# connectors-hw.net
KiCad netlist of a schematic drawn in Altium Designer
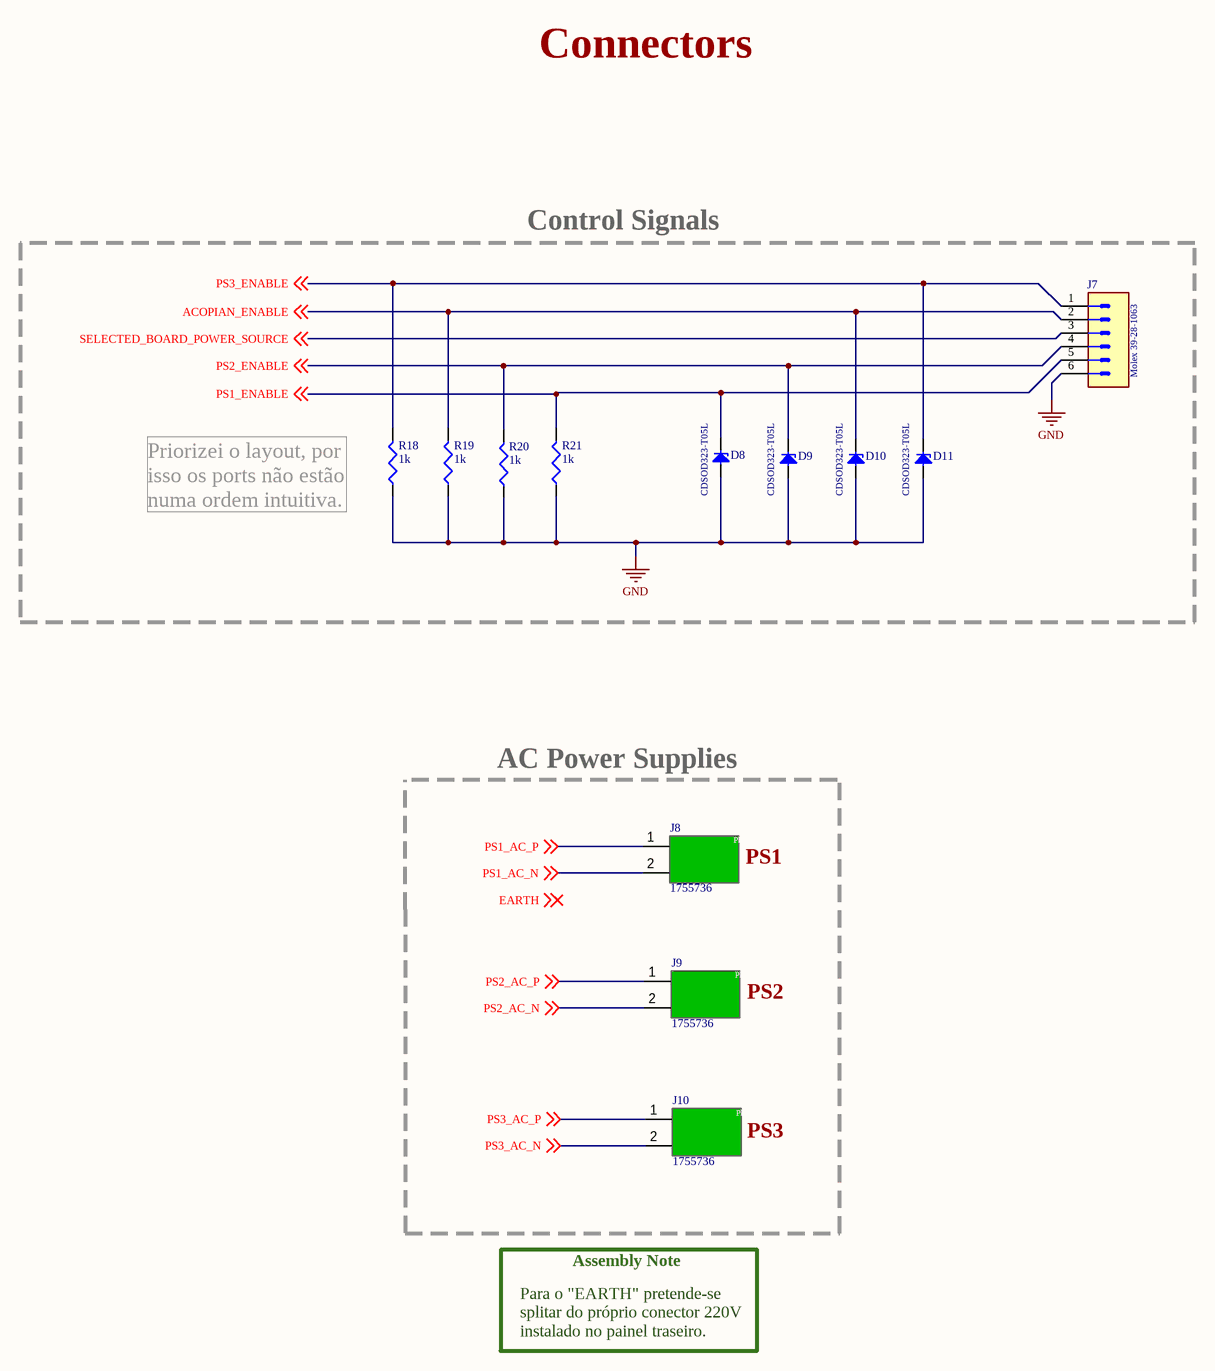
[diagram p0: connectors-hw.SchDoc]

(export (version "E")
  (design (tool "Eeschema 10.0.6"))
  (components
    (comp (ref "D8")
      (value "CDSOD323-T05L")
      (footprint "SOD-323")
      (description "Unidirectional TVS Diode")
      (libsource (lib "acopians-powerspy-ac-power-hw-library-schematic") (part "CDSOD323-T05L"))
    )
    (comp (ref "D9")
      (value "CDSOD323-T05L")
      (footprint "SOD-323")
      (description "Unidirectional TVS Diode")
      (libsource (lib "acopians-powerspy-ac-power-hw-library-schematic") (part "CDSOD323-T05L"))
    )
    (comp (ref "D10")
      (value "CDSOD323-T05L")
      (footprint "SOD-323")
      (description "Unidirectional TVS Diode")
      (libsource (lib "acopians-powerspy-ac-power-hw-library-schematic") (part "CDSOD323-T05L"))
    )
    (comp (ref "D11")
      (value "CDSOD323-T05L")
      (footprint "SOD-323")
      (description "Unidirectional TVS Diode")
      (libsource (lib "acopians-powerspy-ac-power-hw-library-schematic") (part "CDSOD323-T05L"))
    )
    (comp (ref "J7")
      (value "Molex 39-28-1063")
      (footprint "MOLEX_39-28-1063")
      (libsource (lib "acopians-powerspy-ac-power-hw-library-schematic") (part "Connector 6 Male"))
    )
    (comp (ref "J8")
      (value "1755736")
      (footprint "Conector 2 vias")
      (libsource (lib "acopians-powerspy-ac-power-hw-library-schematic") (part "Conector Phoenix 2 vias"))
    )
    (comp (ref "J9")
      (value "1755736")
      (footprint "Conector 2 vias")
      (libsource (lib "acopians-powerspy-ac-power-hw-library-schematic") (part "Conector Phoenix 2 vias"))
    )
    (comp (ref "J10")
      (value "1755736")
      (footprint "Conector 2 vias")
      (libsource (lib "acopians-powerspy-ac-power-hw-library-schematic") (part "Conector Phoenix 2 vias"))
    )
    (comp (ref "R18")
      (value "1k")
      (footprint "Resistor 0805")
      (libsource (lib "acopians-powerspy-ac-power-hw-library-schematic") (part "Resistor 1k"))
    )
    (comp (ref "R19")
      (value "1k")
      (footprint "Resistor 0805")
      (libsource (lib "acopians-powerspy-ac-power-hw-library-schematic") (part "Resistor 1k"))
    )
    (comp (ref "R20")
      (value "1k")
      (footprint "Resistor 0805")
      (libsource (lib "acopians-powerspy-ac-power-hw-library-schematic") (part "Resistor 1k"))
    )
    (comp (ref "R21")
      (value "1k")
      (footprint "Resistor 0805")
      (libsource (lib "acopians-powerspy-ac-power-hw-library-schematic") (part "Resistor 1k"))
    )
  )
  (nets
    (net (code "1") (name "ACOPIAN_ENABLE") (class "Default")
      (node (ref "D10") (pin "1") (pintype "passive"))
      (node (ref "J7") (pin "2") (pinfunction "2_2") (pintype "passive"))
      (node (ref "R19") (pin "2") (pinfunction "2_2") (pintype "passive"))
    )
    (net (code "3") (name "GND") (class "Default")
      (node (ref "D10") (pin "2") (pintype "passive"))
      (node (ref "D11") (pin "2") (pintype "passive"))
      (node (ref "D8") (pin "2") (pintype "passive"))
      (node (ref "D9") (pin "2") (pintype "passive"))
      (node (ref "J7") (pin "6") (pinfunction "6_6") (pintype "passive"))
      (node (ref "R18") (pin "1") (pinfunction "1_1") (pintype "passive"))
      (node (ref "R19") (pin "1") (pinfunction "1_1") (pintype "passive"))
      (node (ref "R20") (pin "1") (pinfunction "1_1") (pintype "passive"))
      (node (ref "R21") (pin "1") (pinfunction "1_1") (pintype "passive"))
    )
    (net (code "4") (name "PS1_AC_N") (class "Default")
      (node (ref "J8") (pin "2") (pinfunction "2_2") (pintype "passive"))
    )
    (net (code "5") (name "PS1_AC_P") (class "Default")
      (node (ref "J8") (pin "1") (pinfunction "1_1") (pintype "passive"))
    )
    (net (code "6") (name "PS1_ENABLE") (class "Default")
      (node (ref "D8") (pin "1") (pintype "passive"))
      (node (ref "J7") (pin "5") (pinfunction "5_5") (pintype "passive"))
      (node (ref "R21") (pin "2") (pinfunction "2_2") (pintype "passive"))
    )
    (net (code "7") (name "PS2_AC_N") (class "Default")
      (node (ref "J9") (pin "2") (pinfunction "2_2") (pintype "passive"))
    )
    (net (code "8") (name "PS2_AC_P") (class "Default")
      (node (ref "J9") (pin "1") (pinfunction "1_1") (pintype "passive"))
    )
    (net (code "9") (name "PS2_ENABLE") (class "Default")
      (node (ref "D9") (pin "1") (pintype "passive"))
      (node (ref "J7") (pin "4") (pinfunction "4_4") (pintype "passive"))
      (node (ref "R20") (pin "2") (pinfunction "2_2") (pintype "passive"))
    )
    (net (code "10") (name "PS3_AC_N") (class "Default")
      (node (ref "J10") (pin "2") (pinfunction "2_2") (pintype "passive"))
    )
    (net (code "11") (name "PS3_AC_P") (class "Default")
      (node (ref "J10") (pin "1") (pinfunction "1_1") (pintype "passive"))
    )
    (net (code "12") (name "PS3_ENABLE") (class "Default")
      (node (ref "D11") (pin "1") (pintype "passive"))
      (node (ref "J7") (pin "1") (pinfunction "1_1") (pintype "passive"))
      (node (ref "R18") (pin "2") (pinfunction "2_2") (pintype "passive"))
    )
    (net (code "13") (name "SELECTED_BOARD_POWER_SOURCE") (class "Default")
      (node (ref "J7") (pin "3") (pinfunction "3_3") (pintype "passive"))
    )
  )
)
